# 4_ch_sample-and-hold_without_mux_v1_0.net
KiCad netlist of a schematic drawn in EAGLE
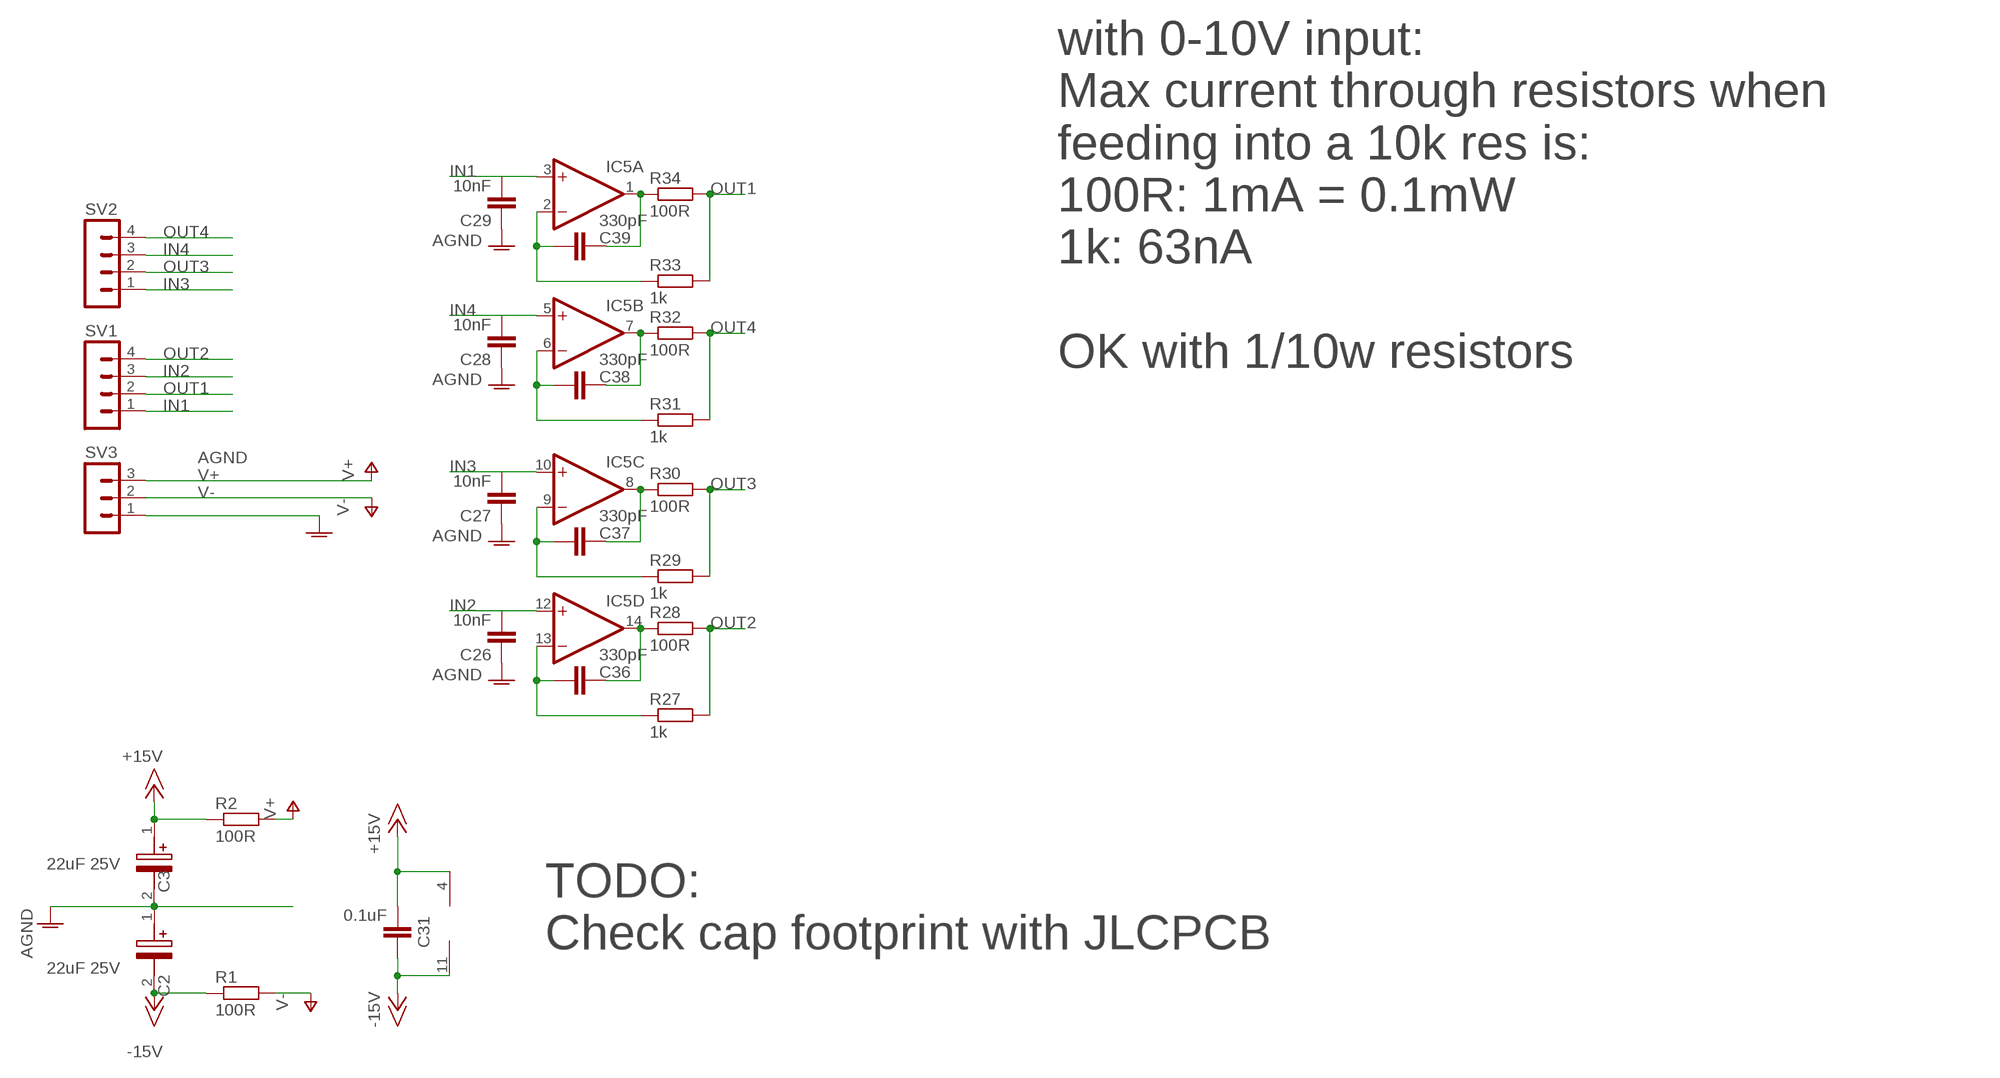
[diagram p0: schematic, sheet 1]

(export (version "E")
  (design (tool "Eeschema 10.0.6"))
  (components
    (comp (ref "C2")
      (value "22uF 25V")
      (footprint "eagle-import:CAPAE660X610N")
      (fields
        (field (name "MANUFACTURER_PART_NUMBER") "VZL101M1CTR-0606")
        (field (name "MOUSER_PART_NUMBER") "140-VZL101M1CTR-0606")
      )
      (libsource (lib "eagle-import") (part "VZL101M1CTR-0606"))
    )
    (comp (ref "C3")
      (value "22uF 25V")
      (footprint "eagle-import:CAPAE660X610N")
      (fields
        (field (name "MANUFACTURER_PART_NUMBER") "VZL101M1CTR-0606")
        (field (name "MOUSER_PART_NUMBER") "140-VZL101M1CTR-0606")
      )
      (libsource (lib "eagle-import") (part "VZL101M1CTR-0606"))
    )
    (comp (ref "C26")
      (value "10nF")
      (footprint "eagle-import:C0805")
      (libsource (lib "eagle-import") (part "C-EUC0805"))
    )
    (comp (ref "C27")
      (value "10nF")
      (footprint "eagle-import:C0805")
      (libsource (lib "eagle-import") (part "C-EUC0805"))
    )
    (comp (ref "C28")
      (value "10nF")
      (footprint "eagle-import:C0805")
      (libsource (lib "eagle-import") (part "C-EUC0805"))
    )
    (comp (ref "C29")
      (value "10nF")
      (footprint "eagle-import:C0805")
      (libsource (lib "eagle-import") (part "C-EUC0805"))
    )
    (comp (ref "C31")
      (value "0.1uF")
      (footprint "eagle-import:C0603")
      (libsource (lib "eagle-import") (part "resistor_C-EUC0603"))
    )
    (comp (ref "C36")
      (value "330pF")
      (footprint "eagle-import:C0603")
      (libsource (lib "eagle-import") (part "resistor_C-EUC0603"))
    )
    (comp (ref "C37")
      (value "330pF")
      (footprint "eagle-import:C0603")
      (libsource (lib "eagle-import") (part "resistor_C-EUC0603"))
    )
    (comp (ref "C38")
      (value "330pF")
      (footprint "eagle-import:C0603")
      (libsource (lib "eagle-import") (part "resistor_C-EUC0603"))
    )
    (comp (ref "C39")
      (value "330pF")
      (footprint "eagle-import:C0603")
      (libsource (lib "eagle-import") (part "resistor_C-EUC0603"))
    )
    (comp (ref "IC5")
      (value "TL074D")
      (footprint "eagle-import:SO14")
      (libsource (lib "eagle-import") (part "TL074D"))
    )
    (comp (ref "R1")
      (value "100R")
      (footprint "eagle-import:R0805")
      (libsource (lib "eagle-import") (part "R-EU_R0805"))
    )
    (comp (ref "R2")
      (value "100R")
      (footprint "eagle-import:R0805")
      (libsource (lib "eagle-import") (part "R-EU_R0805"))
    )
    (comp (ref "R27")
      (value "1k")
      (footprint "eagle-import:R0603")
      (libsource (lib "eagle-import") (part "resistor_R-EU_R0603"))
    )
    (comp (ref "R28")
      (value "100R")
      (footprint "eagle-import:R0603")
      (libsource (lib "eagle-import") (part "resistor_R-EU_R0603"))
    )
    (comp (ref "R29")
      (value "1k")
      (footprint "eagle-import:R0603")
      (libsource (lib "eagle-import") (part "resistor_R-EU_R0603"))
    )
    (comp (ref "R30")
      (value "100R")
      (footprint "eagle-import:R0603")
      (libsource (lib "eagle-import") (part "resistor_R-EU_R0603"))
    )
    (comp (ref "R31")
      (value "1k")
      (footprint "eagle-import:R0603")
      (libsource (lib "eagle-import") (part "resistor_R-EU_R0603"))
    )
    (comp (ref "R32")
      (value "100R")
      (footprint "eagle-import:R0603")
      (libsource (lib "eagle-import") (part "resistor_R-EU_R0603"))
    )
    (comp (ref "R33")
      (value "1k")
      (footprint "eagle-import:R0603")
      (libsource (lib "eagle-import") (part "resistor_R-EU_R0603"))
    )
    (comp (ref "R34")
      (value "100R")
      (footprint "eagle-import:R0603")
      (libsource (lib "eagle-import") (part "resistor_R-EU_R0603"))
    )
    (comp (ref "SV1")
      (value "MA04-1JP")
      (footprint "eagle-import:SIP-PIN04-1J")
      (libsource (lib "eagle-import") (part "MA04-1JP"))
    )
    (comp (ref "SV2")
      (value "MA04-1JP")
      (footprint "eagle-import:SIP-PIN04-1J")
      (libsource (lib "eagle-import") (part "MA04-1JP"))
    )
    (comp (ref "SV3")
      (value "MA03-1JP")
      (footprint "eagle-import:SIP-PIN03-1J")
      (libsource (lib "eagle-import") (part "MA03-1JP"))
    )
  )
  (nets
    (net (code "1") (name "+15V") (class "Default")
      (node (ref "C3") (pin "1") (pinfunction "+_1") (pintype "bidirectional"))
      (node (ref "C31") (pin "1") (pinfunction "1_1") (pintype "passive"))
      (node (ref "IC5") (pin "4") (pinfunction "V+_4") (pintype "power_in"))
      (node (ref "R2") (pin "1") (pinfunction "1_1") (pintype "passive"))
    )
    (net (code "2") (name "-15V") (class "Default")
      (node (ref "C2") (pin "2") (pinfunction "-_2") (pintype "bidirectional"))
      (node (ref "C31") (pin "2") (pinfunction "2_2") (pintype "passive"))
      (node (ref "IC5") (pin "11") (pinfunction "V-_11") (pintype "power_in"))
      (node (ref "R1") (pin "1") (pinfunction "1_1") (pintype "passive"))
    )
    (net (code "3") (name "/IN1") (class "Default")
      (node (ref "C29") (pin "2") (pinfunction "2_2") (pintype "passive"))
      (node (ref "IC5") (pin "3") (pinfunction "+IN_3") (pintype "input"))
      (node (ref "SV1") (pin "1") (pinfunction "1_1") (pintype "passive"))
    )
    (net (code "4") (name "/IN2") (class "Default")
      (node (ref "C26") (pin "2") (pinfunction "2_2") (pintype "passive"))
      (node (ref "IC5") (pin "12") (pinfunction "+IN_12") (pintype "input"))
      (node (ref "SV1") (pin "3") (pinfunction "3_3") (pintype "passive"))
    )
    (net (code "5") (name "/IN3") (class "Default")
      (node (ref "C27") (pin "2") (pinfunction "2_2") (pintype "passive"))
      (node (ref "IC5") (pin "10") (pinfunction "+IN_10") (pintype "input"))
      (node (ref "SV2") (pin "1") (pinfunction "1_1") (pintype "passive"))
    )
    (net (code "6") (name "/IN4") (class "Default")
      (node (ref "C28") (pin "2") (pinfunction "2_2") (pintype "passive"))
      (node (ref "IC5") (pin "5") (pinfunction "+IN_5") (pintype "input"))
      (node (ref "SV2") (pin "3") (pinfunction "3_3") (pintype "passive"))
    )
    (net (code "7") (name "/OUT1") (class "Default")
      (node (ref "R33") (pin "2") (pinfunction "2_2") (pintype "passive"))
      (node (ref "R34") (pin "2") (pinfunction "2_2") (pintype "passive"))
      (node (ref "SV1") (pin "2") (pinfunction "2_2") (pintype "passive"))
    )
    (net (code "8") (name "/OUT2") (class "Default")
      (node (ref "R27") (pin "2") (pinfunction "2_2") (pintype "passive"))
      (node (ref "R28") (pin "2") (pinfunction "2_2") (pintype "passive"))
      (node (ref "SV1") (pin "4") (pinfunction "4_4") (pintype "passive"))
    )
    (net (code "9") (name "/OUT3") (class "Default")
      (node (ref "R29") (pin "2") (pinfunction "2_2") (pintype "passive"))
      (node (ref "R30") (pin "2") (pinfunction "2_2") (pintype "passive"))
      (node (ref "SV2") (pin "2") (pinfunction "2_2") (pintype "passive"))
    )
    (net (code "10") (name "/OUT4") (class "Default")
      (node (ref "R31") (pin "2") (pinfunction "2_2") (pintype "passive"))
      (node (ref "R32") (pin "2") (pinfunction "2_2") (pintype "passive"))
      (node (ref "SV2") (pin "4") (pinfunction "4_4") (pintype "passive"))
    )
    (net (code "11") (name "AGND") (class "Default")
      (node (ref "C2") (pin "1") (pinfunction "+_1") (pintype "bidirectional"))
      (node (ref "C26") (pin "1") (pinfunction "1_1") (pintype "passive"))
      (node (ref "C27") (pin "1") (pinfunction "1_1") (pintype "passive"))
      (node (ref "C28") (pin "1") (pinfunction "1_1") (pintype "passive"))
      (node (ref "C29") (pin "1") (pinfunction "1_1") (pintype "passive"))
      (node (ref "C3") (pin "2") (pinfunction "-_2") (pintype "bidirectional"))
      (node (ref "SV3") (pin "1") (pinfunction "1_1") (pintype "passive"))
    )
    (net (code "12") (name "Net-(IC5A--IN)") (class "Default")
      (node (ref "C39") (pin "2") (pinfunction "2_2") (pintype "passive"))
      (node (ref "IC5") (pin "2") (pinfunction "-IN_2") (pintype "input"))
      (node (ref "R33") (pin "1") (pinfunction "1_1") (pintype "passive"))
    )
    (net (code "13") (name "Net-(IC5A-OUT)") (class "Default")
      (node (ref "C39") (pin "1") (pinfunction "1_1") (pintype "passive"))
      (node (ref "IC5") (pin "1") (pinfunction "OUT_1") (pintype "output"))
      (node (ref "R34") (pin "1") (pinfunction "1_1") (pintype "passive"))
    )
    (net (code "14") (name "Net-(IC5B--IN)") (class "Default")
      (node (ref "C38") (pin "2") (pinfunction "2_2") (pintype "passive"))
      (node (ref "IC5") (pin "6") (pinfunction "-IN_6") (pintype "input"))
      (node (ref "R31") (pin "1") (pinfunction "1_1") (pintype "passive"))
    )
    (net (code "15") (name "Net-(IC5B-OUT)") (class "Default")
      (node (ref "C38") (pin "1") (pinfunction "1_1") (pintype "passive"))
      (node (ref "IC5") (pin "7") (pinfunction "OUT_7") (pintype "output"))
      (node (ref "R32") (pin "1") (pinfunction "1_1") (pintype "passive"))
    )
    (net (code "16") (name "Net-(IC5C--IN)") (class "Default")
      (node (ref "C37") (pin "2") (pinfunction "2_2") (pintype "passive"))
      (node (ref "IC5") (pin "9") (pinfunction "-IN_9") (pintype "input"))
      (node (ref "R29") (pin "1") (pinfunction "1_1") (pintype "passive"))
    )
    (net (code "17") (name "Net-(IC5C-OUT)") (class "Default")
      (node (ref "C37") (pin "1") (pinfunction "1_1") (pintype "passive"))
      (node (ref "IC5") (pin "8") (pinfunction "OUT_8") (pintype "output"))
      (node (ref "R30") (pin "1") (pinfunction "1_1") (pintype "passive"))
    )
    (net (code "18") (name "Net-(IC5D--IN)") (class "Default")
      (node (ref "C36") (pin "2") (pinfunction "2_2") (pintype "passive"))
      (node (ref "IC5") (pin "13") (pinfunction "-IN_13") (pintype "input"))
      (node (ref "R27") (pin "1") (pinfunction "1_1") (pintype "passive"))
    )
    (net (code "19") (name "Net-(IC5D-OUT)") (class "Default")
      (node (ref "C36") (pin "1") (pinfunction "1_1") (pintype "passive"))
      (node (ref "IC5") (pin "14") (pinfunction "OUT_14") (pintype "output"))
      (node (ref "R28") (pin "1") (pinfunction "1_1") (pintype "passive"))
    )
    (net (code "20") (name "V+") (class "Default")
      (node (ref "R2") (pin "2") (pinfunction "2_2") (pintype "passive"))
      (node (ref "SV3") (pin "3") (pinfunction "3_3") (pintype "passive"))
    )
    (net (code "21") (name "V-") (class "Default")
      (node (ref "R1") (pin "2") (pinfunction "2_2") (pintype "passive"))
      (node (ref "SV3") (pin "2") (pinfunction "2_2") (pintype "passive"))
    )
  )
)
